# design.net
KiCad netlist of a schematic drawn in Altium Designer
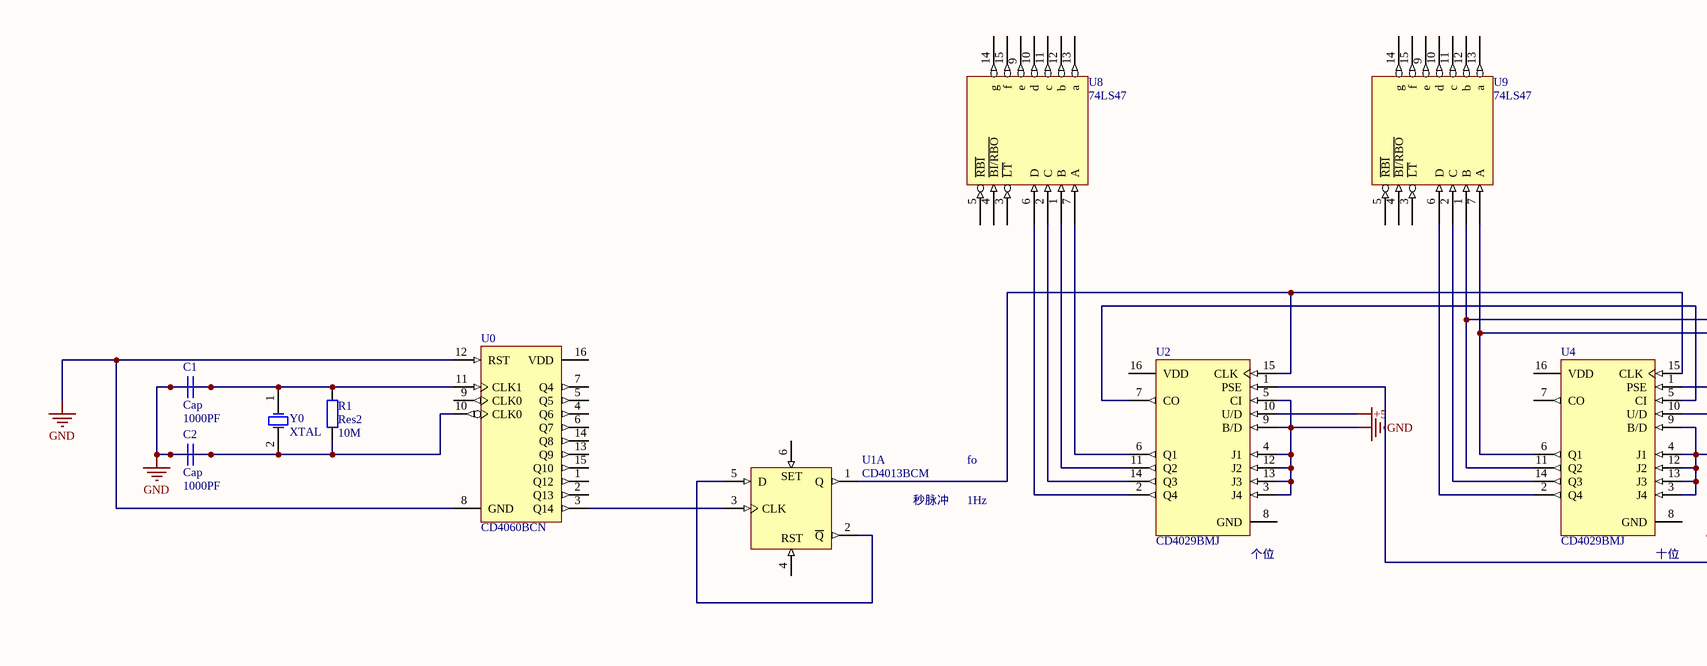
[diagram p0: 原理总图.SchDoc, left]
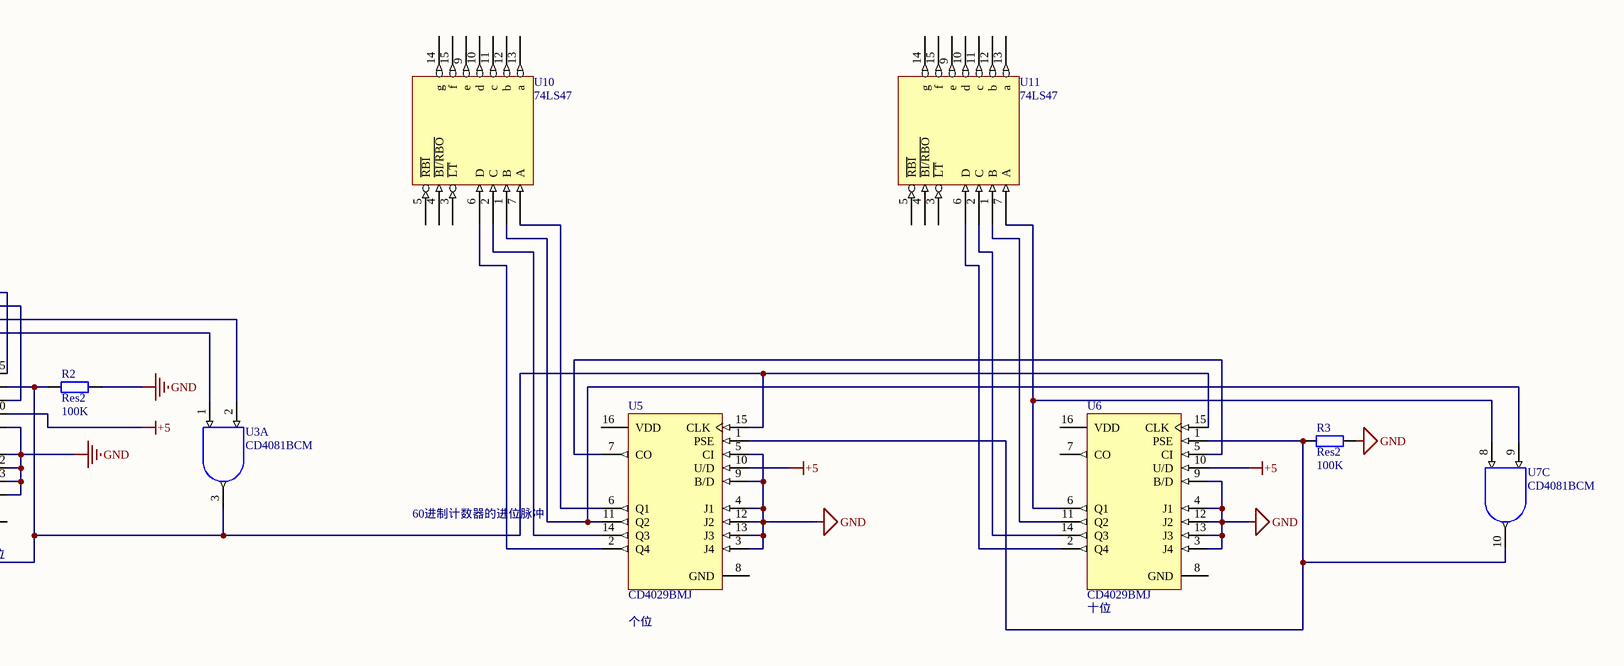
[diagram p1: 原理总图.SchDoc, right]

(export (version "E")
  (design (tool "Eeschema 10.0.6"))
  (components
    (comp (ref "C1")
      (value "Cap")
      (footprint "RAD-0.3")
      (description "Capacitor")
      (fields (field (name "ALTIUM_VALUE") "1000PF") (field (name "PUBLISHER") "Altium Limited"))
      (libsource (lib "Miscellaneous Devices") (part "Cap"))
    )
    (comp (ref "C2")
      (value "Cap")
      (footprint "RAD-0.3")
      (description "Capacitor")
      (fields (field (name "ALTIUM_VALUE") "1000PF") (field (name "PUBLISHER") "Altium Limited"))
      (libsource (lib "Miscellaneous Devices") (part "Cap"))
    )
    (comp (ref "R1")
      (value "Res2")
      (footprint "AXIAL-0.4")
      (description "Resistor")
      (fields (field (name "ALTIUM_VALUE") "10M") (field (name "PUBLISHER") "Altium Limited"))
      (libsource (lib "") (part "Res2_1"))
    )
    (comp (ref "R2")
      (value "Res2")
      (footprint "AXIAL-0.4")
      (description "Resistor")
      (fields (field (name "ALTIUM_VALUE") "100K") (field (name "PUBLISHER") "Altium Limited"))
      (libsource (lib "Miscellaneous Devices") (part "Res2"))
    )
    (comp (ref "R3")
      (value "Res2")
      (footprint "AXIAL-0.4")
      (description "Resistor")
      (fields (field (name "ALTIUM_VALUE") "100K") (field (name "PUBLISHER") "Altium Limited"))
      (libsource (lib "Miscellaneous Devices") (part "Res2"))
    )
    (comp (ref "U0")
      (value "CD4060BCN")
      (footprint "N16E")
      (description "14-Stage Ripple Carry Binary Counter")
      (fields (field (name "PUBLISHER") "Altium Limited"))
      (libsource (lib "NSC Logic Counter") (part "CD4060BCN"))
    )
    (comp (ref "U1")
      (value "CD4013BCM")
      (footprint "M14A_N")
      (description "Dual D-Type Flip-Flop")
      (fields (field (name "PUBLISHER") "Altium Limited"))
      (libsource (lib "FSC Logic Flip-Flop") (part "CD4013BCM"))
    )
    (comp (ref "U2")
      (value "CD4029BMJ")
      (footprint "J16A")
      (description "Binary/Decade Up/Down Counter")
      (fields (field (name "PUBLISHER") "Altium Limited"))
      (libsource (lib "NSC Logic Counter") (part "CD4029BMJ"))
    )
    (comp (ref "U3")
      (value "CD4081BCM")
      (footprint "M14A_N")
      (description "Quad 2-Input AND Buffered B series Gate, 14-Pin SOIC")
      (fields (field (name "PUBLISHER") "Altium Limited"))
      (libsource (lib "FSC Logic Gate") (part "CD4081BCM"))
    )
    (comp (ref "U4")
      (value "CD4029BMJ")
      (footprint "J16A")
      (description "Binary/Decade Up/Down Counter")
      (fields (field (name "PUBLISHER") "Altium Limited"))
      (libsource (lib "NSC Logic Counter") (part "CD4029BMJ"))
    )
    (comp (ref "U5")
      (value "CD4029BMJ")
      (footprint "J16A")
      (description "Binary/Decade Up/Down Counter")
      (fields (field (name "PUBLISHER") "Altium Limited"))
      (libsource (lib "NSC Logic Counter") (part "CD4029BMJ"))
    )
    (comp (ref "U6")
      (value "CD4029BMJ")
      (footprint "J16A")
      (description "Binary/Decade Up/Down Counter")
      (fields (field (name "PUBLISHER") "Altium Limited"))
      (libsource (lib "NSC Logic Counter") (part "CD4029BMJ"))
    )
    (comp (ref "U7")
      (value "CD4081BCM")
      (footprint "M14A_N")
      (description "Quad 2-Input AND Buffered B series Gate, 14-Pin SOIC")
      (fields (field (name "PUBLISHER") "Altium Limited"))
      (libsource (lib "FSC Logic Gate") (part "CD4081BCM"))
    )
    (comp (ref "U8")
      (value "74LS47")
      (footprint "DIP-16")
      (libsource (lib "Protel DOS Schematic Libraries") (part "74LS47"))
    )
    (comp (ref "U9")
      (value "74LS47")
      (footprint "DIP-16")
      (libsource (lib "Protel DOS Schematic Libraries") (part "74LS47"))
    )
    (comp (ref "U10")
      (value "74LS47")
      (footprint "DIP-16")
      (libsource (lib "Protel DOS Schematic Libraries") (part "74LS47"))
    )
    (comp (ref "U11")
      (value "74LS47")
      (footprint "DIP-16")
      (libsource (lib "Protel DOS Schematic Libraries") (part "74LS47"))
    )
    (comp (ref "Y0")
      (value "XTAL")
      (footprint "R38")
      (description "Crystal Oscillator")
      (fields (field (name "PUBLISHER") "Altium Limited"))
      (libsource (lib "Miscellaneous Devices") (part "XTAL"))
    )
  )
  (nets
    (net (code "1") (name "+5") (class "Default")
      (node (ref "U2") (pin "10") (pinfunction "U/D_10") (pintype "input"))
      (node (ref "U4") (pin "10") (pinfunction "U/D_10") (pintype "input"))
      (node (ref "U5") (pin "10") (pinfunction "U/D_10") (pintype "input"))
      (node (ref "U6") (pin "10") (pinfunction "U/D_10") (pintype "input"))
    )
    (net (code "2") (name "GND") (class "Default")
      (node (ref "C1") (pin "1") (pinfunction "1_1") (pintype "passive"))
      (node (ref "C1") (pin "2") (pinfunction "2_2") (pintype "passive"))
      (node (ref "C2") (pin "1") (pinfunction "1_1") (pintype "passive"))
      (node (ref "C2") (pin "2") (pinfunction "2_2") (pintype "passive"))
      (node (ref "R1") (pin "1") (pinfunction "1_1") (pintype "passive"))
      (node (ref "R1") (pin "2") (pinfunction "2_2") (pintype "passive"))
      (node (ref "R2") (pin "1") (pinfunction "1_1") (pintype "passive"))
      (node (ref "R3") (pin "1") (pinfunction "1_1") (pintype "passive"))
      (node (ref "U0") (pin "10") (pinfunction "CLK0_10") (pintype "output"))
      (node (ref "U0") (pin "11") (pinfunction "CLK1_11") (pintype "input"))
      (node (ref "U0") (pin "12") (pinfunction "RST_12") (pintype "input"))
      (node (ref "U0") (pin "8") (pinfunction "GND_8") (pintype "power_in"))
      (node (ref "U1") (pin "7") (pinfunction "GND_7") (pintype "power_in"))
      (node (ref "U10") (pin "8") (pinfunction "GND_8") (pintype "power_in"))
      (node (ref "U11") (pin "8") (pinfunction "GND_8") (pintype "power_in"))
      (node (ref "U2") (pin "12") (pinfunction "J2_12") (pintype "input"))
      (node (ref "U2") (pin "13") (pinfunction "J3_13") (pintype "input"))
      (node (ref "U2") (pin "3") (pinfunction "J4_3") (pintype "input"))
      (node (ref "U2") (pin "4") (pinfunction "J1_4") (pintype "input"))
      (node (ref "U2") (pin "5") (pinfunction "CI_5") (pintype "input"))
      (node (ref "U2") (pin "9") (pinfunction "B/D_9") (pintype "input"))
      (node (ref "U3") (pin "7") (pinfunction "GND_7") (pintype "power_in"))
      (node (ref "U4") (pin "12") (pinfunction "J2_12") (pintype "input"))
      (node (ref "U4") (pin "13") (pinfunction "J3_13") (pintype "input"))
      (node (ref "U4") (pin "3") (pinfunction "J4_3") (pintype "input"))
      (node (ref "U4") (pin "4") (pinfunction "J1_4") (pintype "input"))
      (node (ref "U4") (pin "9") (pinfunction "B/D_9") (pintype "input"))
      (node (ref "U5") (pin "12") (pinfunction "J2_12") (pintype "input"))
      (node (ref "U5") (pin "13") (pinfunction "J3_13") (pintype "input"))
      (node (ref "U5") (pin "3") (pinfunction "J4_3") (pintype "input"))
      (node (ref "U5") (pin "4") (pinfunction "J1_4") (pintype "input"))
      (node (ref "U5") (pin "5") (pinfunction "CI_5") (pintype "input"))
      (node (ref "U5") (pin "9") (pinfunction "B/D_9") (pintype "input"))
      (node (ref "U6") (pin "12") (pinfunction "J2_12") (pintype "input"))
      (node (ref "U6") (pin "13") (pinfunction "J3_13") (pintype "input"))
      (node (ref "U6") (pin "3") (pinfunction "J4_3") (pintype "input"))
      (node (ref "U6") (pin "4") (pinfunction "J1_4") (pintype "input"))
      (node (ref "U6") (pin "9") (pinfunction "B/D_9") (pintype "input"))
      (node (ref "U7") (pin "7") (pinfunction "GND_7") (pintype "power_in"))
      (node (ref "U8") (pin "8") (pinfunction "GND_8") (pintype "power_in"))
      (node (ref "U9") (pin "8") (pinfunction "GND_8") (pintype "power_in"))
      (node (ref "Y0") (pin "1") (pinfunction "OSC1_1") (pintype "passive"))
      (node (ref "Y0") (pin "2") (pinfunction "OSC2_2") (pintype "passive"))
    )
    (net (code "3") (name "Net-(U0-Q14)") (class "Default")
      (node (ref "U0") (pin "3") (pinfunction "Q14_3") (pintype "output"))
      (node (ref "U1") (pin "3") (pinfunction "CLK_3") (pintype "input"))
    )
    (net (code "4") (name "Net-(U1A-D)") (class "Default")
      (node (ref "U1") (pin "2") (pinfunction "~{Q}_2") (pintype "output"))
      (node (ref "U1") (pin "5") (pinfunction "D_5") (pintype "input"))
    )
    (net (code "5") (name "Net-(U1A-Q)") (class "Default")
      (node (ref "U1") (pin "1") (pinfunction "Q_1") (pintype "output"))
      (node (ref "U2") (pin "15") (pinfunction "CLK_15") (pintype "input"))
      (node (ref "U4") (pin "15") (pinfunction "CLK_15") (pintype "input"))
    )
    (net (code "6") (name "Net-(U2-CO)") (class "Default")
      (node (ref "U2") (pin "7") (pinfunction "CO_7") (pintype "output"))
      (node (ref "U4") (pin "5") (pinfunction "CI_5") (pintype "input"))
    )
    (net (code "7") (name "Net-(U2-PSE)") (class "Default")
      (node (ref "R2") (pin "2") (pinfunction "2_2") (pintype "passive"))
      (node (ref "U2") (pin "1") (pinfunction "PSE_1") (pintype "input"))
      (node (ref "U3") (pin "3") (pinfunction "J_3") (pintype "output"))
      (node (ref "U4") (pin "1") (pinfunction "PSE_1") (pintype "input"))
      (node (ref "U5") (pin "15") (pinfunction "CLK_15") (pintype "input"))
      (node (ref "U6") (pin "15") (pinfunction "CLK_15") (pintype "input"))
    )
    (net (code "8") (name "Net-(U2-Q1)") (class "Default")
      (node (ref "U2") (pin "6") (pinfunction "Q1_6") (pintype "output"))
      (node (ref "U8") (pin "7") (pinfunction "A_7") (pintype "input"))
    )
    (net (code "9") (name "Net-(U2-Q2)") (class "Default")
      (node (ref "U2") (pin "11") (pinfunction "Q2_11") (pintype "output"))
      (node (ref "U8") (pin "1") (pinfunction "B_1") (pintype "input"))
    )
    (net (code "10") (name "Net-(U2-Q3)") (class "Default")
      (node (ref "U2") (pin "14") (pinfunction "Q3_14") (pintype "output"))
      (node (ref "U8") (pin "2") (pinfunction "C_2") (pintype "input"))
    )
    (net (code "11") (name "Net-(U2-Q4)") (class "Default")
      (node (ref "U2") (pin "2") (pinfunction "Q4_2") (pintype "output"))
      (node (ref "U8") (pin "6") (pinfunction "D_6") (pintype "input"))
    )
    (net (code "12") (name "Net-(U3A-A)") (class "Default")
      (node (ref "U3") (pin "1") (pinfunction "A_1") (pintype "input"))
      (node (ref "U4") (pin "6") (pinfunction "Q1_6") (pintype "output"))
      (node (ref "U9") (pin "7") (pinfunction "A_7") (pintype "input"))
    )
    (net (code "13") (name "Net-(U3A-B)") (class "Default")
      (node (ref "U3") (pin "2") (pinfunction "B_2") (pintype "input"))
      (node (ref "U4") (pin "11") (pinfunction "Q2_11") (pintype "output"))
      (node (ref "U9") (pin "1") (pinfunction "B_1") (pintype "input"))
    )
    (net (code "14") (name "Net-(U4-Q3)") (class "Default")
      (node (ref "U4") (pin "14") (pinfunction "Q3_14") (pintype "output"))
      (node (ref "U9") (pin "2") (pinfunction "C_2") (pintype "input"))
    )
    (net (code "15") (name "Net-(U4-Q4)") (class "Default")
      (node (ref "U4") (pin "2") (pinfunction "Q4_2") (pintype "output"))
      (node (ref "U9") (pin "6") (pinfunction "D_6") (pintype "input"))
    )
    (net (code "16") (name "Net-(U5-CO)") (class "Default")
      (node (ref "U5") (pin "7") (pinfunction "CO_7") (pintype "output"))
      (node (ref "U6") (pin "5") (pinfunction "CI_5") (pintype "input"))
    )
    (net (code "17") (name "Net-(U5-PSE)") (class "Default")
      (node (ref "R3") (pin "2") (pinfunction "2_2") (pintype "passive"))
      (node (ref "U5") (pin "1") (pinfunction "PSE_1") (pintype "input"))
      (node (ref "U6") (pin "1") (pinfunction "PSE_1") (pintype "input"))
      (node (ref "U7") (pin "10") (pinfunction "J_10") (pintype "output"))
    )
    (net (code "18") (name "Net-(U10-A)") (class "Default")
      (node (ref "U10") (pin "7") (pinfunction "A_7") (pintype "input"))
      (node (ref "U5") (pin "6") (pinfunction "Q1_6") (pintype "output"))
    )
    (net (code "19") (name "Net-(U10-B)") (class "Default")
      (node (ref "U10") (pin "1") (pinfunction "B_1") (pintype "input"))
      (node (ref "U5") (pin "11") (pinfunction "Q2_11") (pintype "output"))
      (node (ref "U7") (pin "9") (pinfunction "B_9") (pintype "input"))
    )
    (net (code "20") (name "Net-(U10-C)") (class "Default")
      (node (ref "U10") (pin "2") (pinfunction "C_2") (pintype "input"))
      (node (ref "U5") (pin "14") (pinfunction "Q3_14") (pintype "output"))
    )
    (net (code "21") (name "Net-(U10-D)") (class "Default")
      (node (ref "U10") (pin "6") (pinfunction "D_6") (pintype "input"))
      (node (ref "U5") (pin "2") (pinfunction "Q4_2") (pintype "output"))
    )
    (net (code "22") (name "Net-(U11-A)") (class "Default")
      (node (ref "U11") (pin "7") (pinfunction "A_7") (pintype "input"))
      (node (ref "U6") (pin "6") (pinfunction "Q1_6") (pintype "output"))
      (node (ref "U7") (pin "8") (pinfunction "A_8") (pintype "input"))
    )
    (net (code "23") (name "Net-(U11-B)") (class "Default")
      (node (ref "U11") (pin "1") (pinfunction "B_1") (pintype "input"))
      (node (ref "U6") (pin "11") (pinfunction "Q2_11") (pintype "output"))
    )
    (net (code "24") (name "Net-(U11-C)") (class "Default")
      (node (ref "U11") (pin "2") (pinfunction "C_2") (pintype "input"))
      (node (ref "U6") (pin "14") (pinfunction "Q3_14") (pintype "output"))
    )
    (net (code "25") (name "Net-(U11-D)") (class "Default")
      (node (ref "U11") (pin "6") (pinfunction "D_6") (pintype "input"))
      (node (ref "U6") (pin "2") (pinfunction "Q4_2") (pintype "output"))
    )
    (net (code "26") (name "VCC") (class "Default")
      (node (ref "U10") (pin "16") (pinfunction "VCC_16") (pintype "power_in"))
      (node (ref "U11") (pin "16") (pinfunction "VCC_16") (pintype "power_in"))
      (node (ref "U8") (pin "16") (pinfunction "VCC_16") (pintype "power_in"))
      (node (ref "U9") (pin "16") (pinfunction "VCC_16") (pintype "power_in"))
    )
    (net (code "27") (name "VDD") (class "Default")
      (node (ref "U1") (pin "14") (pinfunction "VDD_14") (pintype "power_in"))
      (node (ref "U3") (pin "14") (pinfunction "VDD_14") (pintype "power_in"))
      (node (ref "U7") (pin "14") (pinfunction "VDD_14") (pintype "power_in"))
    )
    (net (code "28") (name "unconnected-(U0-CLK0-Pad9)") (class "Default")
      (node (ref "U0") (pin "9") (pinfunction "CLK0_9") (pintype "output"))
    )
    (net (code "29") (name "unconnected-(U0-Q4-Pad7)") (class "Default")
      (node (ref "U0") (pin "7") (pinfunction "Q4_7") (pintype "output"))
    )
    (net (code "30") (name "unconnected-(U0-Q5-Pad5)") (class "Default")
      (node (ref "U0") (pin "5") (pinfunction "Q5_5") (pintype "output"))
    )
    (net (code "31") (name "unconnected-(U0-Q6-Pad4)") (class "Default")
      (node (ref "U0") (pin "4") (pinfunction "Q6_4") (pintype "output"))
    )
    (net (code "32") (name "unconnected-(U0-Q7-Pad6)") (class "Default")
      (node (ref "U0") (pin "6") (pinfunction "Q7_6") (pintype "output"))
    )
    (net (code "33") (name "unconnected-(U0-Q8-Pad14)") (class "Default")
      (node (ref "U0") (pin "14") (pinfunction "Q8_14") (pintype "output"))
    )
    (net (code "34") (name "unconnected-(U0-Q9-Pad13)") (class "Default")
      (node (ref "U0") (pin "13") (pinfunction "Q9_13") (pintype "output"))
    )
    (net (code "35") (name "unconnected-(U0-Q10-Pad15)") (class "Default")
      (node (ref "U0") (pin "15") (pinfunction "Q10_15") (pintype "output"))
    )
    (net (code "36") (name "unconnected-(U0-Q12-Pad1)") (class "Default")
      (node (ref "U0") (pin "1") (pinfunction "Q12_1") (pintype "output"))
    )
    (net (code "37") (name "unconnected-(U0-Q13-Pad2)") (class "Default")
      (node (ref "U0") (pin "2") (pinfunction "Q13_2") (pintype "output"))
    )
    (net (code "38") (name "unconnected-(U0-VDD-Pad16)") (class "Default")
      (node (ref "U0") (pin "16") (pinfunction "VDD_16") (pintype "power_in"))
    )
    (net (code "39") (name "unconnected-(U1A-RST-Pad4)") (class "Default")
      (node (ref "U1") (pin "4") (pinfunction "RST_4") (pintype "input"))
    )
    (net (code "40") (name "unconnected-(U1A-S-Pad6)") (class "Default")
      (node (ref "U1") (pin "6") (pinfunction "S_6") (pintype "input"))
    )
    (net (code "41") (name "unconnected-(U2-GND-Pad8)") (class "Default")
      (node (ref "U2") (pin "8") (pinfunction "GND_8") (pintype "power_in"))
    )
    (net (code "42") (name "unconnected-(U2-VDD-Pad16)") (class "Default")
      (node (ref "U2") (pin "16") (pinfunction "VDD_16") (pintype "power_in"))
    )
    (net (code "43") (name "unconnected-(U4-CO-Pad7)") (class "Default")
      (node (ref "U4") (pin "7") (pinfunction "CO_7") (pintype "output"))
    )
    (net (code "44") (name "unconnected-(U4-GND-Pad8)") (class "Default")
      (node (ref "U4") (pin "8") (pinfunction "GND_8") (pintype "power_in"))
    )
    (net (code "45") (name "unconnected-(U4-VDD-Pad16)") (class "Default")
      (node (ref "U4") (pin "16") (pinfunction "VDD_16") (pintype "power_in"))
    )
    (net (code "46") (name "unconnected-(U5-GND-Pad8)") (class "Default")
      (node (ref "U5") (pin "8") (pinfunction "GND_8") (pintype "power_in"))
    )
    (net (code "47") (name "unconnected-(U5-VDD-Pad16)") (class "Default")
      (node (ref "U5") (pin "16") (pinfunction "VDD_16") (pintype "power_in"))
    )
    (net (code "48") (name "unconnected-(U6-CO-Pad7)") (class "Default")
      (node (ref "U6") (pin "7") (pinfunction "CO_7") (pintype "output"))
    )
    (net (code "49") (name "unconnected-(U6-GND-Pad8)") (class "Default")
      (node (ref "U6") (pin "8") (pinfunction "GND_8") (pintype "power_in"))
    )
    (net (code "50") (name "unconnected-(U6-VDD-Pad16)") (class "Default")
      (node (ref "U6") (pin "16") (pinfunction "VDD_16") (pintype "power_in"))
    )
    (net (code "51") (name "unconnected-(U8-a-Pad13)") (class "Default")
      (node (ref "U8") (pin "13") (pinfunction "a_13") (pintype "output"))
    )
    (net (code "52") (name "unconnected-(U8-b-Pad12)") (class "Default")
      (node (ref "U8") (pin "12") (pinfunction "b_12") (pintype "output"))
    )
    (net (code "53") (name "unconnected-(U8-c-Pad11)") (class "Default")
      (node (ref "U8") (pin "11") (pinfunction "c_11") (pintype "output"))
    )
    (net (code "54") (name "unconnected-(U8-d-Pad10)") (class "Default")
      (node (ref "U8") (pin "10") (pinfunction "d_10") (pintype "output"))
    )
    (net (code "55") (name "unconnected-(U8-e-Pad9)") (class "Default")
      (node (ref "U8") (pin "9") (pinfunction "e_9") (pintype "output"))
    )
    (net (code "56") (name "unconnected-(U8-f-Pad15)") (class "Default")
      (node (ref "U8") (pin "15") (pinfunction "f_15") (pintype "output"))
    )
    (net (code "57") (name "unconnected-(U8-g-Pad14)") (class "Default")
      (node (ref "U8") (pin "14") (pinfunction "g_14") (pintype "output"))
    )
    (net (code "58") (name "unconnected-(U8-~{BI{slash}RBO}-Pad4)") (class "Default")
      (node (ref "U8") (pin "4") (pinfunction "~{BI/RBO}_4") (pintype "input"))
    )
    (net (code "59") (name "unconnected-(U8-~{LT}-Pad3)") (class "Default")
      (node (ref "U8") (pin "3") (pinfunction "~{LT}_3") (pintype "input"))
    )
    (net (code "60") (name "unconnected-(U8-~{RBI}-Pad5)") (class "Default")
      (node (ref "U8") (pin "5") (pinfunction "~{RBI}_5") (pintype "input"))
    )
    (net (code "61") (name "unconnected-(U9-a-Pad13)") (class "Default")
      (node (ref "U9") (pin "13") (pinfunction "a_13") (pintype "output"))
    )
    (net (code "62") (name "unconnected-(U9-b-Pad12)") (class "Default")
      (node (ref "U9") (pin "12") (pinfunction "b_12") (pintype "output"))
    )
    (net (code "63") (name "unconnected-(U9-c-Pad11)") (class "Default")
      (node (ref "U9") (pin "11") (pinfunction "c_11") (pintype "output"))
    )
    (net (code "64") (name "unconnected-(U9-d-Pad10)") (class "Default")
      (node (ref "U9") (pin "10") (pinfunction "d_10") (pintype "output"))
    )
    (net (code "65") (name "unconnected-(U9-e-Pad9)") (class "Default")
      (node (ref "U9") (pin "9") (pinfunction "e_9") (pintype "output"))
    )
    (net (code "66") (name "unconnected-(U9-f-Pad15)") (class "Default")
      (node (ref "U9") (pin "15") (pinfunction "f_15") (pintype "output"))
    )
    (net (code "67") (name "unconnected-(U9-g-Pad14)") (class "Default")
      (node (ref "U9") (pin "14") (pinfunction "g_14") (pintype "output"))
    )
    (net (code "68") (name "unconnected-(U9-~{BI{slash}RBO}-Pad4)") (class "Default")
      (node (ref "U9") (pin "4") (pinfunction "~{BI/RBO}_4") (pintype "input"))
    )
    (net (code "69") (name "unconnected-(U9-~{LT}-Pad3)") (class "Default")
      (node (ref "U9") (pin "3") (pinfunction "~{LT}_3") (pintype "input"))
    )
    (net (code "70") (name "unconnected-(U9-~{RBI}-Pad5)") (class "Default")
      (node (ref "U9") (pin "5") (pinfunction "~{RBI}_5") (pintype "input"))
    )
    (net (code "71") (name "unconnected-(U10-a-Pad13)") (class "Default")
      (node (ref "U10") (pin "13") (pinfunction "a_13") (pintype "output"))
    )
    (net (code "72") (name "unconnected-(U10-b-Pad12)") (class "Default")
      (node (ref "U10") (pin "12") (pinfunction "b_12") (pintype "output"))
    )
    (net (code "73") (name "unconnected-(U10-c-Pad11)") (class "Default")
      (node (ref "U10") (pin "11") (pinfunction "c_11") (pintype "output"))
    )
    (net (code "74") (name "unconnected-(U10-d-Pad10)") (class "Default")
      (node (ref "U10") (pin "10") (pinfunction "d_10") (pintype "output"))
    )
    (net (code "75") (name "unconnected-(U10-e-Pad9)") (class "Default")
      (node (ref "U10") (pin "9") (pinfunction "e_9") (pintype "output"))
    )
    (net (code "76") (name "unconnected-(U10-f-Pad15)") (class "Default")
      (node (ref "U10") (pin "15") (pinfunction "f_15") (pintype "output"))
    )
    (net (code "77") (name "unconnected-(U10-g-Pad14)") (class "Default")
      (node (ref "U10") (pin "14") (pinfunction "g_14") (pintype "output"))
    )
    (net (code "78") (name "unconnected-(U10-~{BI{slash}RBO}-Pad4)") (class "Default")
      (node (ref "U10") (pin "4") (pinfunction "~{BI/RBO}_4") (pintype "input"))
    )
    (net (code "79") (name "unconnected-(U10-~{LT}-Pad3)") (class "Default")
      (node (ref "U10") (pin "3") (pinfunction "~{LT}_3") (pintype "input"))
    )
    (net (code "80") (name "unconnected-(U10-~{RBI}-Pad5)") (class "Default")
      (node (ref "U10") (pin "5") (pinfunction "~{RBI}_5") (pintype "input"))
    )
    (net (code "81") (name "unconnected-(U11-a-Pad13)") (class "Default")
      (node (ref "U11") (pin "13") (pinfunction "a_13") (pintype "output"))
    )
    (net (code "82") (name "unconnected-(U11-b-Pad12)") (class "Default")
      (node (ref "U11") (pin "12") (pinfunction "b_12") (pintype "output"))
    )
    (net (code "83") (name "unconnected-(U11-c-Pad11)") (class "Default")
      (node (ref "U11") (pin "11") (pinfunction "c_11") (pintype "output"))
    )
    (net (code "84") (name "unconnected-(U11-d-Pad10)") (class "Default")
      (node (ref "U11") (pin "10") (pinfunction "d_10") (pintype "output"))
    )
    (net (code "85") (name "unconnected-(U11-e-Pad9)") (class "Default")
      (node (ref "U11") (pin "9") (pinfunction "e_9") (pintype "output"))
    )
    (net (code "86") (name "unconnected-(U11-f-Pad15)") (class "Default")
      (node (ref "U11") (pin "15") (pinfunction "f_15") (pintype "output"))
    )
    (net (code "87") (name "unconnected-(U11-g-Pad14)") (class "Default")
      (node (ref "U11") (pin "14") (pinfunction "g_14") (pintype "output"))
    )
    (net (code "88") (name "unconnected-(U11-~{BI{slash}RBO}-Pad4)") (class "Default")
      (node (ref "U11") (pin "4") (pinfunction "~{BI/RBO}_4") (pintype "input"))
    )
    (net (code "89") (name "unconnected-(U11-~{LT}-Pad3)") (class "Default")
      (node (ref "U11") (pin "3") (pinfunction "~{LT}_3") (pintype "input"))
    )
    (net (code "90") (name "unconnected-(U11-~{RBI}-Pad5)") (class "Default")
      (node (ref "U11") (pin "5") (pinfunction "~{RBI}_5") (pintype "input"))
    )
  )
)
